# motorcontroller_10_01_2017.net
KiCad netlist of a schematic drawn in EAGLE
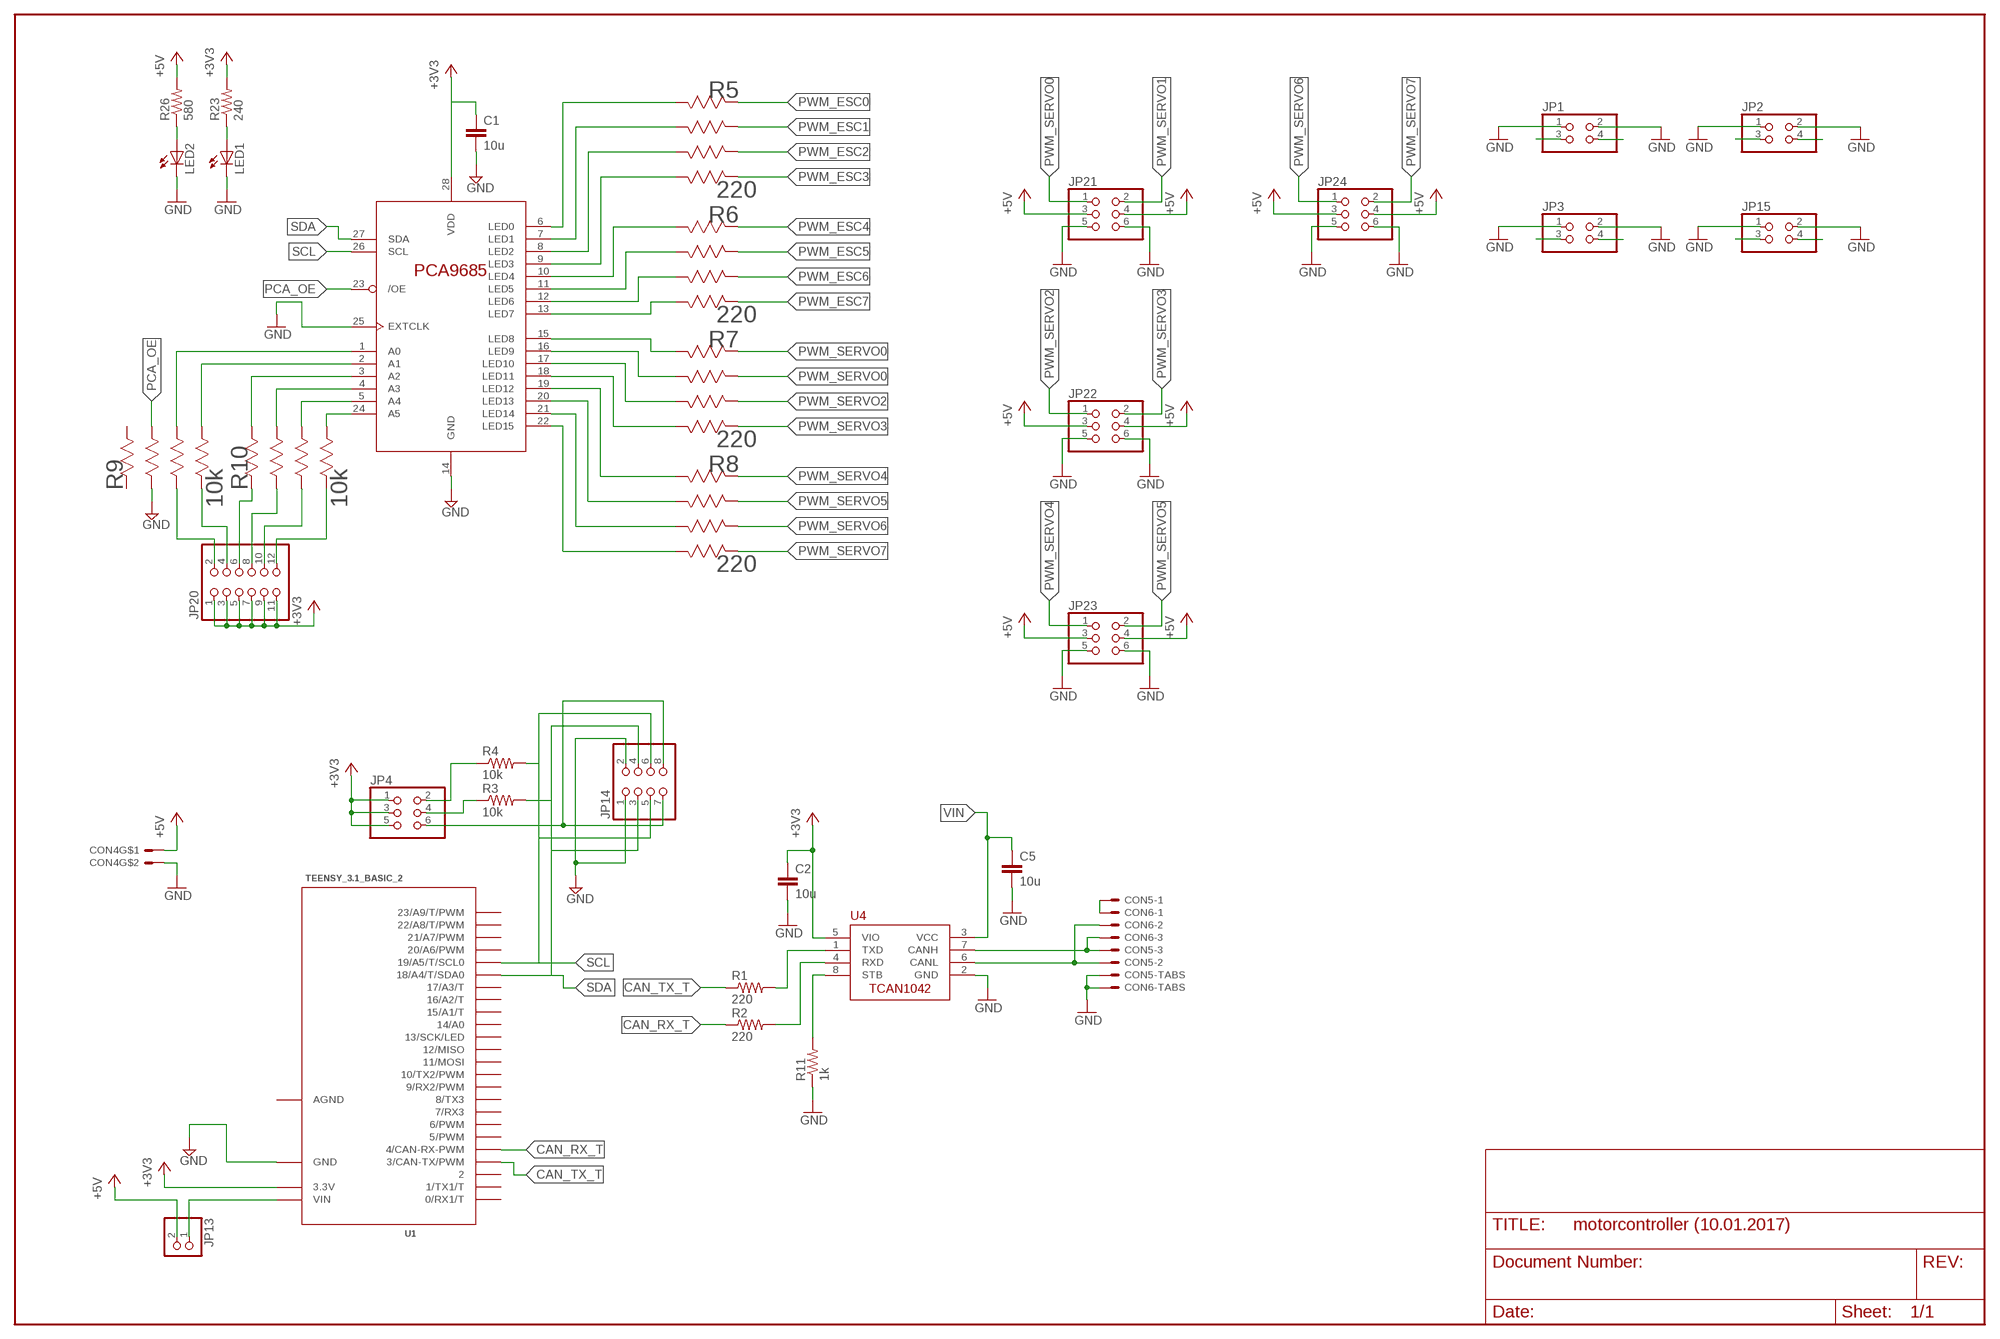
[diagram p0: schematic, sheet 1]

(export (version "E")
  (design (tool "Eeschema 10.0.6"))
  (components
    (comp (ref "C1")
      (value "10u")
      (footprint "eagle-import:C0805")
      (libsource (lib "eagle-import") (part "C-EUC0805"))
    )
    (comp (ref "C2")
      (value "10u")
      (footprint "eagle-import:C0805")
      (libsource (lib "eagle-import") (part "C-EUC0805"))
    )
    (comp (ref "C5")
      (value "10u")
      (footprint "eagle-import:C0805")
      (libsource (lib "eagle-import") (part "C-EUC0805"))
    )
    (comp (ref "CON4")
      (value "MOLEX_5566-2")
      (footprint "eagle-import:5566-2")
      (libsource (lib "eagle-import") (part "MOLEX_5566-2"))
    )
    (comp (ref "CON5")
      (value "S3B-PH-SM4-TB")
      (footprint "eagle-import:S3B-PH-SM4-TB")
      (libsource (lib "eagle-import") (part "S3B-PH-SM4-TB"))
    )
    (comp (ref "CON6")
      (value "S3B-PH-SM4-TB")
      (footprint "eagle-import:S3B-PH-SM4-TB")
      (libsource (lib "eagle-import") (part "S3B-PH-SM4-TB"))
    )
    (comp (ref "JP1")
      (value "PINHD-2X2")
      (footprint "eagle-import:2X02")
      (libsource (lib "eagle-import") (part "PINHD-2X2"))
    )
    (comp (ref "JP2")
      (value "PINHD-2X2")
      (footprint "eagle-import:2X02")
      (libsource (lib "eagle-import") (part "PINHD-2X2"))
    )
    (comp (ref "JP3")
      (value "PINHD-2X2")
      (footprint "eagle-import:2X02")
      (libsource (lib "eagle-import") (part "PINHD-2X2"))
    )
    (comp (ref "JP4")
      (value "PINHD-2X3")
      (footprint "eagle-import:2X03")
      (libsource (lib "eagle-import") (part "PINHD-2X3"))
    )
    (comp (ref "JP13")
      (value "PINHD-1X2")
      (footprint "eagle-import:1X02")
      (libsource (lib "eagle-import") (part "PINHD-1X2"))
    )
    (comp (ref "JP14")
      (value "PINHD-2X4")
      (footprint "eagle-import:2X04")
      (libsource (lib "eagle-import") (part "PINHD-2X4"))
    )
    (comp (ref "JP15")
      (value "PINHD-2X2")
      (footprint "eagle-import:2X02")
      (libsource (lib "eagle-import") (part "PINHD-2X2"))
    )
    (comp (ref "JP20")
      (value "PINHD-2X6")
      (footprint "eagle-import:2X06")
      (libsource (lib "eagle-import") (part "PINHD-2X6"))
    )
    (comp (ref "JP21")
      (value "PINHD-2X3")
      (footprint "eagle-import:2X03")
      (libsource (lib "eagle-import") (part "PINHD-2X3"))
    )
    (comp (ref "JP22")
      (value "PINHD-2X3")
      (footprint "eagle-import:2X03")
      (libsource (lib "eagle-import") (part "PINHD-2X3"))
    )
    (comp (ref "JP23")
      (value "PINHD-2X3")
      (footprint "eagle-import:2X03")
      (libsource (lib "eagle-import") (part "PINHD-2X3"))
    )
    (comp (ref "JP24")
      (value "PINHD-2X3")
      (footprint "eagle-import:2X03")
      (libsource (lib "eagle-import") (part "PINHD-2X3"))
    )
    (comp (ref "LED1")
      (value "LEDCHIPLED_1206")
      (footprint "eagle-import:CHIPLED_1206")
      (libsource (lib "eagle-import") (part "LEDCHIPLED_1206"))
    )
    (comp (ref "LED2")
      (value "LEDCHIPLED_1206")
      (footprint "eagle-import:CHIPLED_1206")
      (libsource (lib "eagle-import") (part "LEDCHIPLED_1206"))
    )
    (comp (ref "R1")
      (value "220")
      (footprint "eagle-import:R0805")
      (libsource (lib "eagle-import") (part "R-US_R0805"))
    )
    (comp (ref "R2")
      (value "220")
      (footprint "eagle-import:R0805")
      (libsource (lib "eagle-import") (part "R-US_R0805"))
    )
    (comp (ref "R3")
      (value "10k")
      (footprint "eagle-import:R1206")
      (libsource (lib "eagle-import") (part "R-US_R1206"))
    )
    (comp (ref "R4")
      (value "10k")
      (footprint "eagle-import:R1206")
      (libsource (lib "eagle-import") (part "R-US_R1206"))
    )
    (comp (ref "R5")
      (value "220")
      (footprint "eagle-import:EXBV8V-M")
      (fields (field (name "MANUFACTURER_PART_NUMBER") "EXBV8V221JV"))
      (libsource (lib "eagle-import") (part "EXB-V8V221JVEXBV8V-M"))
    )
    (comp (ref "R6")
      (value "220")
      (footprint "eagle-import:EXBV8V-M")
      (fields (field (name "MANUFACTURER_PART_NUMBER") "EXBV8V221JV"))
      (libsource (lib "eagle-import") (part "EXB-V8V221JVEXBV8V-M"))
    )
    (comp (ref "R7")
      (value "220")
      (footprint "eagle-import:EXBV8V-M")
      (fields (field (name "MANUFACTURER_PART_NUMBER") "EXBV8V221JV"))
      (libsource (lib "eagle-import") (part "EXB-V8V221JVEXBV8V-M"))
    )
    (comp (ref "R8")
      (value "220")
      (footprint "eagle-import:EXBV8V-M")
      (fields (field (name "MANUFACTURER_PART_NUMBER") "EXBV8V221JV"))
      (libsource (lib "eagle-import") (part "EXB-V8V221JVEXBV8V-M"))
    )
    (comp (ref "R9")
      (value "10k")
      (footprint "eagle-import:EXBV8V-M")
      (fields (field (name "MANUFACTURER_PART_NUMBER") "EXBV8V221JV"))
      (libsource (lib "eagle-import") (part "EXB-V8V221JVEXBV8V-M"))
    )
    (comp (ref "R10")
      (value "10k")
      (footprint "eagle-import:EXBV8V-M")
      (fields (field (name "MANUFACTURER_PART_NUMBER") "EXBV8V221JV"))
      (libsource (lib "eagle-import") (part "EXB-V8V221JVEXBV8V-M"))
    )
    (comp (ref "R11")
      (value "1k")
      (footprint "eagle-import:R0805")
      (libsource (lib "eagle-import") (part "R-US_R0805"))
    )
    (comp (ref "R23")
      (value "240")
      (footprint "eagle-import:R1206")
      (libsource (lib "eagle-import") (part "R-US_R1206"))
    )
    (comp (ref "R26")
      (value "580")
      (footprint "eagle-import:R1206")
      (libsource (lib "eagle-import") (part "R-US_R1206"))
    )
    (comp (ref "U1")
      (value "TEENSY_3.1_BASIC_2")
      (footprint "eagle-import:TEENSY_3.1_BASIC_2")
      (libsource (lib "eagle-import") (part "TEENSY_3.1_BASIC_2"))
    )
    (comp (ref "U2")
      (value "PCA9685PW")
      (footprint "eagle-import:TSSOP28")
      (libsource (lib "eagle-import") (part "PCA9685PW"))
    )
    (comp (ref "U4")
      (value "TCAN1042HVDR")
      (footprint "eagle-import:SO-8")
      (libsource (lib "eagle-import") (part "TCAN1042HVDR"))
    )
  )
  (nets
    (net (code "1") (name "+3V3") (class "Default")
      (node (ref "C1") (pin "1") (pinfunction "1_1") (pintype "passive"))
      (node (ref "C2") (pin "1") (pinfunction "1_1") (pintype "passive"))
      (node (ref "JP20") (pin "1") (pinfunction "1_1") (pintype "passive"))
      (node (ref "JP20") (pin "11") (pinfunction "11_11") (pintype "passive"))
      (node (ref "JP20") (pin "3") (pinfunction "3_3") (pintype "passive"))
      (node (ref "JP20") (pin "5") (pinfunction "5_5") (pintype "passive"))
      (node (ref "JP20") (pin "7") (pinfunction "7_7") (pintype "passive"))
      (node (ref "JP20") (pin "9") (pinfunction "9_9") (pintype "passive"))
      (node (ref "JP4") (pin "1") (pinfunction "1_1") (pintype "passive"))
      (node (ref "JP4") (pin "3") (pinfunction "3_3") (pintype "passive"))
      (node (ref "JP4") (pin "5") (pinfunction "5_5") (pintype "passive"))
      (node (ref "R23") (pin "2") (pinfunction "2_2") (pintype "passive"))
      (node (ref "U1") (pin "3.3V") (pinfunction "3.3V_3.3V") (pintype "power_in"))
      (node (ref "U2") (pin "28") (pinfunction "VDD_28") (pintype "power_in"))
      (node (ref "U4") (pin "5") (pinfunction "VIO_5") (pintype "bidirectional"))
    )
    (net (code "2") (name "+5V") (class "Default")
      (node (ref "CON4") (pin "1") (pinfunction "S_1") (pintype "passive"))
      (node (ref "JP13") (pin "2") (pinfunction "2_2") (pintype "passive"))
      (node (ref "JP21") (pin "3") (pinfunction "3_3") (pintype "passive"))
      (node (ref "JP21") (pin "4") (pinfunction "4_4") (pintype "passive"))
      (node (ref "JP22") (pin "3") (pinfunction "3_3") (pintype "passive"))
      (node (ref "JP22") (pin "4") (pinfunction "4_4") (pintype "passive"))
      (node (ref "JP23") (pin "3") (pinfunction "3_3") (pintype "passive"))
      (node (ref "JP23") (pin "4") (pinfunction "4_4") (pintype "passive"))
      (node (ref "JP24") (pin "3") (pinfunction "3_3") (pintype "passive"))
      (node (ref "JP24") (pin "4") (pinfunction "4_4") (pintype "passive"))
      (node (ref "R26") (pin "2") (pinfunction "2_2") (pintype "passive"))
    )
    (net (code "3") (name "/AGND") (class "Default")
      (node (ref "U1") (pin "AGND") (pinfunction "AGND_AGND") (pintype "power_in"))
    )
    (net (code "4") (name "CAN_RX_T") (class "Default")
      (node (ref "R2") (pin "1") (pinfunction "1_1") (pintype "passive"))
      (node (ref "U1") (pin "4") (pinfunction "4/CAN-RX-PWM_4") (pintype "bidirectional"))
    )
    (net (code "5") (name "CAN_TX_T") (class "Default")
      (node (ref "R1") (pin "1") (pinfunction "1_1") (pintype "passive"))
      (node (ref "U1") (pin "3") (pinfunction "3/CAN-TX/PWM_3") (pintype "bidirectional"))
    )
    (net (code "6") (name "GND") (class "Default")
      (node (ref "C1") (pin "2") (pinfunction "2_2") (pintype "passive"))
      (node (ref "C2") (pin "2") (pinfunction "2_2") (pintype "passive"))
      (node (ref "C5") (pin "2") (pinfunction "2_2") (pintype "passive"))
      (node (ref "CON4") (pin "2") (pinfunction "S_2") (pintype "passive"))
      (node (ref "CON5") (pin "P$4") (pinfunction "S_P$4") (pintype "passive"))
      (node (ref "CON5") (pin "P$5") (pinfunction "S_P$5") (pintype "passive"))
      (node (ref "CON6") (pin "P$4") (pinfunction "S_P$4") (pintype "passive"))
      (node (ref "CON6") (pin "P$5") (pinfunction "S_P$5") (pintype "passive"))
      (node (ref "JP1") (pin "1") (pinfunction "1_1") (pintype "passive"))
      (node (ref "JP1") (pin "2") (pinfunction "2_2") (pintype "passive"))
      (node (ref "JP14") (pin "1") (pinfunction "1_1") (pintype "passive"))
      (node (ref "JP14") (pin "2") (pinfunction "2_2") (pintype "passive"))
      (node (ref "JP15") (pin "1") (pinfunction "1_1") (pintype "passive"))
      (node (ref "JP15") (pin "2") (pinfunction "2_2") (pintype "passive"))
      (node (ref "JP2") (pin "1") (pinfunction "1_1") (pintype "passive"))
      (node (ref "JP2") (pin "2") (pinfunction "2_2") (pintype "passive"))
      (node (ref "JP21") (pin "5") (pinfunction "5_5") (pintype "passive"))
      (node (ref "JP21") (pin "6") (pinfunction "6_6") (pintype "passive"))
      (node (ref "JP22") (pin "5") (pinfunction "5_5") (pintype "passive"))
      (node (ref "JP22") (pin "6") (pinfunction "6_6") (pintype "passive"))
      (node (ref "JP23") (pin "5") (pinfunction "5_5") (pintype "passive"))
      (node (ref "JP23") (pin "6") (pinfunction "6_6") (pintype "passive"))
      (node (ref "JP24") (pin "5") (pinfunction "5_5") (pintype "passive"))
      (node (ref "JP24") (pin "6") (pinfunction "6_6") (pintype "passive"))
      (node (ref "JP3") (pin "1") (pinfunction "1_1") (pintype "passive"))
      (node (ref "JP3") (pin "2") (pinfunction "2_2") (pintype "passive"))
      (node (ref "LED1") (pin "C") (pinfunction "C_C") (pintype "passive"))
      (node (ref "LED2") (pin "C") (pinfunction "C_C") (pintype "passive"))
      (node (ref "R11") (pin "1") (pinfunction "1_1") (pintype "passive"))
      (node (ref "R9") (pin "2") (pinfunction "23_2") (pintype "passive"))
      (node (ref "U1") (pin "GND") (pinfunction "GND_GND") (pintype "power_in"))
      (node (ref "U2") (pin "14") (pinfunction "GND_14") (pintype "power_in"))
      (node (ref "U2") (pin "25") (pinfunction "EXTCLK_25") (pintype "input"))
      (node (ref "U4") (pin "2") (pinfunction "GND_2") (pintype "bidirectional"))
    )
    (net (code "7") (name "Net-(CON5A-S)") (class "Default")
      (node (ref "CON5") (pin "P$1") (pinfunction "S_P$1") (pintype "passive"))
      (node (ref "CON6") (pin "P$1") (pinfunction "S_P$1") (pintype "passive"))
    )
    (net (code "8") (name "Net-(CON5B-S)") (class "Default")
      (node (ref "CON5") (pin "P$2") (pinfunction "S_P$2") (pintype "passive"))
      (node (ref "CON6") (pin "P$2") (pinfunction "S_P$2") (pintype "passive"))
      (node (ref "U4") (pin "6") (pinfunction "CANL_6") (pintype "bidirectional"))
    )
    (net (code "9") (name "Net-(CON5C-S)") (class "Default")
      (node (ref "CON5") (pin "P$3") (pinfunction "S_P$3") (pintype "passive"))
      (node (ref "CON6") (pin "P$3") (pinfunction "S_P$3") (pintype "passive"))
      (node (ref "U4") (pin "7") (pinfunction "CANH_7") (pintype "bidirectional"))
    )
    (net (code "10") (name "Net-(JP4-Pad2)") (class "Default")
      (node (ref "JP4") (pin "2") (pinfunction "2_2") (pintype "passive"))
      (node (ref "R4") (pin "1") (pinfunction "1_1") (pintype "passive"))
    )
    (net (code "11") (name "Net-(JP4-Pad4)") (class "Default")
      (node (ref "JP4") (pin "4") (pinfunction "4_4") (pintype "passive"))
      (node (ref "R3") (pin "1") (pinfunction "1_1") (pintype "passive"))
    )
    (net (code "12") (name "Net-(JP14-Pad7)") (class "Default")
      (node (ref "JP14") (pin "7") (pinfunction "7_7") (pintype "passive"))
      (node (ref "JP14") (pin "8") (pinfunction "8_8") (pintype "passive"))
      (node (ref "JP4") (pin "6") (pinfunction "6_6") (pintype "passive"))
    )
    (net (code "13") (name "Net-(LED1-PadA)") (class "Default")
      (node (ref "LED1") (pin "A") (pinfunction "A_A") (pintype "passive"))
      (node (ref "R23") (pin "1") (pinfunction "1_1") (pintype "passive"))
    )
    (net (code "14") (name "Net-(LED2-PadA)") (class "Default")
      (node (ref "LED2") (pin "A") (pinfunction "A_A") (pintype "passive"))
      (node (ref "R26") (pin "1") (pinfunction "1_1") (pintype "passive"))
    )
    (net (code "15") (name "Net-(R5-58)") (class "Default")
      (node (ref "R5") (pin "5") (pinfunction "58_5") (pintype "passive"))
      (node (ref "U2") (pin "9") (pinfunction "LED3_9") (pintype "bidirectional"))
    )
    (net (code "16") (name "Net-(R5-66)") (class "Default")
      (node (ref "R5") (pin "6") (pinfunction "66_6") (pintype "passive"))
      (node (ref "U2") (pin "8") (pinfunction "LED2_8") (pintype "bidirectional"))
    )
    (net (code "17") (name "Net-(R5-74)") (class "Default")
      (node (ref "R5") (pin "7") (pinfunction "74_7") (pintype "passive"))
      (node (ref "U2") (pin "7") (pinfunction "LED1_7") (pintype "bidirectional"))
    )
    (net (code "18") (name "Net-(R5-82)") (class "Default")
      (node (ref "R5") (pin "8") (pinfunction "82_8") (pintype "passive"))
      (node (ref "U2") (pin "6") (pinfunction "LED0_6") (pintype "bidirectional"))
    )
    (net (code "19") (name "Net-(R6-58)") (class "Default")
      (node (ref "R6") (pin "5") (pinfunction "58_5") (pintype "passive"))
      (node (ref "U2") (pin "13") (pinfunction "LED7_13") (pintype "bidirectional"))
    )
    (net (code "20") (name "Net-(R6-66)") (class "Default")
      (node (ref "R6") (pin "6") (pinfunction "66_6") (pintype "passive"))
      (node (ref "U2") (pin "12") (pinfunction "LED6_12") (pintype "bidirectional"))
    )
    (net (code "21") (name "Net-(R6-74)") (class "Default")
      (node (ref "R6") (pin "7") (pinfunction "74_7") (pintype "passive"))
      (node (ref "U2") (pin "11") (pinfunction "LED5_11") (pintype "bidirectional"))
    )
    (net (code "22") (name "Net-(R6-82)") (class "Default")
      (node (ref "R6") (pin "8") (pinfunction "82_8") (pintype "passive"))
      (node (ref "U2") (pin "10") (pinfunction "LED4_10") (pintype "bidirectional"))
    )
    (net (code "23") (name "Net-(R7-58)") (class "Default")
      (node (ref "R7") (pin "5") (pinfunction "58_5") (pintype "passive"))
      (node (ref "U2") (pin "18") (pinfunction "LED11_18") (pintype "bidirectional"))
    )
    (net (code "24") (name "Net-(R7-66)") (class "Default")
      (node (ref "R7") (pin "6") (pinfunction "66_6") (pintype "passive"))
      (node (ref "U2") (pin "17") (pinfunction "LED10_17") (pintype "bidirectional"))
    )
    (net (code "25") (name "Net-(R7-74)") (class "Default")
      (node (ref "R7") (pin "7") (pinfunction "74_7") (pintype "passive"))
      (node (ref "U2") (pin "16") (pinfunction "LED9_16") (pintype "bidirectional"))
    )
    (net (code "26") (name "Net-(R7-82)") (class "Default")
      (node (ref "R7") (pin "8") (pinfunction "82_8") (pintype "passive"))
      (node (ref "U2") (pin "15") (pinfunction "LED8_15") (pintype "bidirectional"))
    )
    (net (code "27") (name "Net-(R8-58)") (class "Default")
      (node (ref "R8") (pin "5") (pinfunction "58_5") (pintype "passive"))
      (node (ref "U2") (pin "22") (pinfunction "LED15_22") (pintype "bidirectional"))
    )
    (net (code "28") (name "Net-(R8-66)") (class "Default")
      (node (ref "R8") (pin "6") (pinfunction "66_6") (pintype "passive"))
      (node (ref "U2") (pin "21") (pinfunction "LED14_21") (pintype "bidirectional"))
    )
    (net (code "29") (name "Net-(R8-74)") (class "Default")
      (node (ref "R8") (pin "7") (pinfunction "74_7") (pintype "passive"))
      (node (ref "U2") (pin "20") (pinfunction "LED13_20") (pintype "bidirectional"))
    )
    (net (code "30") (name "Net-(R8-82)") (class "Default")
      (node (ref "R8") (pin "8") (pinfunction "82_8") (pintype "passive"))
      (node (ref "U2") (pin "19") (pinfunction "LED12_19") (pintype "bidirectional"))
    )
    (net (code "31") (name "Net-(R9-35)") (class "Default")
      (node (ref "JP20") (pin "2") (pinfunction "2_2") (pintype "passive"))
      (node (ref "R9") (pin "3") (pinfunction "35_3") (pintype "passive"))
    )
    (net (code "32") (name "Net-(R9-47)") (class "Default")
      (node (ref "JP20") (pin "4") (pinfunction "4_4") (pintype "passive"))
      (node (ref "R9") (pin "4") (pinfunction "47_4") (pintype "passive"))
    )
    (net (code "33") (name "Net-(R9-58)") (class "Default")
      (node (ref "R9") (pin "5") (pinfunction "58_5") (pintype "passive"))
      (node (ref "U2") (pin "2") (pinfunction "A1_2") (pintype "bidirectional"))
    )
    (net (code "34") (name "Net-(R9-66)") (class "Default")
      (node (ref "R9") (pin "6") (pinfunction "66_6") (pintype "passive"))
      (node (ref "U2") (pin "1") (pinfunction "A0_1") (pintype "bidirectional"))
    )
    (net (code "35") (name "Net-(R10-11)") (class "Default")
      (node (ref "JP20") (pin "6") (pinfunction "6_6") (pintype "passive"))
      (node (ref "R10") (pin "1") (pinfunction "11_1") (pintype "passive"))
    )
    (net (code "36") (name "Net-(R10-23)") (class "Default")
      (node (ref "JP20") (pin "8") (pinfunction "8_8") (pintype "passive"))
      (node (ref "R10") (pin "2") (pinfunction "23_2") (pintype "passive"))
    )
    (net (code "37") (name "Net-(R10-35)") (class "Default")
      (node (ref "JP20") (pin "10") (pinfunction "10_10") (pintype "passive"))
      (node (ref "R10") (pin "3") (pinfunction "35_3") (pintype "passive"))
    )
    (net (code "38") (name "Net-(R10-47)") (class "Default")
      (node (ref "JP20") (pin "12") (pinfunction "12_12") (pintype "passive"))
      (node (ref "R10") (pin "4") (pinfunction "47_4") (pintype "passive"))
    )
    (net (code "39") (name "Net-(R10-58)") (class "Default")
      (node (ref "R10") (pin "5") (pinfunction "58_5") (pintype "passive"))
      (node (ref "U2") (pin "24") (pinfunction "A5_24") (pintype "bidirectional"))
    )
    (net (code "40") (name "Net-(R10-66)") (class "Default")
      (node (ref "R10") (pin "6") (pinfunction "66_6") (pintype "passive"))
      (node (ref "U2") (pin "5") (pinfunction "A4_5") (pintype "bidirectional"))
    )
    (net (code "41") (name "Net-(R10-74)") (class "Default")
      (node (ref "R10") (pin "7") (pinfunction "74_7") (pintype "passive"))
      (node (ref "U2") (pin "4") (pinfunction "A3_4") (pintype "bidirectional"))
    )
    (net (code "42") (name "Net-(R10-82)") (class "Default")
      (node (ref "R10") (pin "8") (pinfunction "82_8") (pintype "passive"))
      (node (ref "U2") (pin "3") (pinfunction "A2_3") (pintype "bidirectional"))
    )
    (net (code "43") (name "Net-(U4-RXD)") (class "Default")
      (node (ref "R2") (pin "2") (pinfunction "2_2") (pintype "passive"))
      (node (ref "U4") (pin "4") (pinfunction "RXD_4") (pintype "bidirectional"))
    )
    (net (code "44") (name "Net-(U4-STB)") (class "Default")
      (node (ref "R11") (pin "2") (pinfunction "2_2") (pintype "passive"))
      (node (ref "U4") (pin "8") (pinfunction "STB_8") (pintype "bidirectional"))
    )
    (net (code "45") (name "Net-(U4-TXD)") (class "Default")
      (node (ref "R1") (pin "2") (pinfunction "2_2") (pintype "passive"))
      (node (ref "U4") (pin "1") (pinfunction "TXD_1") (pintype "bidirectional"))
    )
    (net (code "46") (name "PCA_OE") (class "Default")
      (node (ref "R9") (pin "7") (pinfunction "74_7") (pintype "passive"))
      (node (ref "U2") (pin "23") (pinfunction "/OE_23") (pintype "bidirectional"))
    )
    (net (code "47") (name "PWM_ESC0") (class "Default")
      (node (ref "JP15") (pin "4") (pinfunction "4_4") (pintype "passive"))
      (node (ref "R5") (pin "1") (pinfunction "11_1") (pintype "passive"))
    )
    (net (code "48") (name "PWM_ESC1") (class "Default")
      (node (ref "JP15") (pin "3") (pinfunction "3_3") (pintype "passive"))
      (node (ref "R5") (pin "2") (pinfunction "23_2") (pintype "passive"))
    )
    (net (code "49") (name "PWM_ESC2") (class "Default")
      (node (ref "JP1") (pin "4") (pinfunction "4_4") (pintype "passive"))
      (node (ref "R5") (pin "3") (pinfunction "35_3") (pintype "passive"))
    )
    (net (code "50") (name "PWM_ESC3") (class "Default")
      (node (ref "JP1") (pin "3") (pinfunction "3_3") (pintype "passive"))
      (node (ref "R5") (pin "4") (pinfunction "47_4") (pintype "passive"))
    )
    (net (code "51") (name "PWM_ESC4") (class "Default")
      (node (ref "JP2") (pin "4") (pinfunction "4_4") (pintype "passive"))
      (node (ref "R6") (pin "1") (pinfunction "11_1") (pintype "passive"))
    )
    (net (code "52") (name "PWM_ESC5") (class "Default")
      (node (ref "JP2") (pin "3") (pinfunction "3_3") (pintype "passive"))
      (node (ref "R6") (pin "2") (pinfunction "23_2") (pintype "passive"))
    )
    (net (code "53") (name "PWM_ESC6") (class "Default")
      (node (ref "JP3") (pin "4") (pinfunction "4_4") (pintype "passive"))
      (node (ref "R6") (pin "3") (pinfunction "35_3") (pintype "passive"))
    )
    (net (code "54") (name "PWM_ESC7") (class "Default")
      (node (ref "JP3") (pin "3") (pinfunction "3_3") (pintype "passive"))
      (node (ref "R6") (pin "4") (pinfunction "47_4") (pintype "passive"))
    )
    (net (code "55") (name "PWM_SERVO0") (class "Default")
      (node (ref "JP21") (pin "1") (pinfunction "1_1") (pintype "passive"))
      (node (ref "R7") (pin "1") (pinfunction "11_1") (pintype "passive"))
    )
    (net (code "56") (name "PWM_SERVO1") (class "Default")
      (node (ref "JP21") (pin "2") (pinfunction "2_2") (pintype "passive"))
      (node (ref "R7") (pin "2") (pinfunction "23_2") (pintype "passive"))
    )
    (net (code "57") (name "PWM_SERVO2") (class "Default")
      (node (ref "JP22") (pin "1") (pinfunction "1_1") (pintype "passive"))
      (node (ref "R7") (pin "3") (pinfunction "35_3") (pintype "passive"))
    )
    (net (code "58") (name "PWM_SERVO3") (class "Default")
      (node (ref "JP22") (pin "2") (pinfunction "2_2") (pintype "passive"))
      (node (ref "R7") (pin "4") (pinfunction "47_4") (pintype "passive"))
    )
    (net (code "59") (name "PWM_SERVO4") (class "Default")
      (node (ref "JP23") (pin "1") (pinfunction "1_1") (pintype "passive"))
      (node (ref "R8") (pin "1") (pinfunction "11_1") (pintype "passive"))
    )
    (net (code "60") (name "PWM_SERVO5") (class "Default")
      (node (ref "JP23") (pin "2") (pinfunction "2_2") (pintype "passive"))
      (node (ref "R8") (pin "2") (pinfunction "23_2") (pintype "passive"))
    )
    (net (code "61") (name "PWM_SERVO6") (class "Default")
      (node (ref "JP24") (pin "1") (pinfunction "1_1") (pintype "passive"))
      (node (ref "R8") (pin "3") (pinfunction "35_3") (pintype "passive"))
    )
    (net (code "62") (name "PWM_SERVO7") (class "Default")
      (node (ref "JP24") (pin "2") (pinfunction "2_2") (pintype "passive"))
      (node (ref "R8") (pin "4") (pinfunction "47_4") (pintype "passive"))
    )
    (net (code "63") (name "SCL") (class "Default")
      (node (ref "JP14") (pin "5") (pinfunction "5_5") (pintype "passive"))
      (node (ref "JP14") (pin "6") (pinfunction "6_6") (pintype "passive"))
      (node (ref "R4") (pin "2") (pinfunction "2_2") (pintype "passive"))
      (node (ref "U1") (pin "19/A5") (pinfunction "19/A5/T/SCL0_19/A5") (pintype "bidirectional"))
      (node (ref "U2") (pin "26") (pinfunction "SCL_26") (pintype "bidirectional"))
    )
    (net (code "64") (name "SDA") (class "Default")
      (node (ref "JP14") (pin "3") (pinfunction "3_3") (pintype "passive"))
      (node (ref "JP14") (pin "4") (pinfunction "4_4") (pintype "passive"))
      (node (ref "R3") (pin "2") (pinfunction "2_2") (pintype "passive"))
      (node (ref "U1") (pin "18/A4") (pinfunction "18/A4/T/SDA0_18/A4") (pintype "bidirectional"))
      (node (ref "U2") (pin "27") (pinfunction "SDA_27") (pintype "bidirectional"))
    )
    (net (code "65") (name "VIN") (class "Default")
      (node (ref "C5") (pin "1") (pinfunction "1_1") (pintype "passive"))
      (node (ref "JP13") (pin "1") (pinfunction "1_1") (pintype "passive"))
      (node (ref "U1") (pin "VIN") (pinfunction "VIN_VIN") (pintype "power_in"))
      (node (ref "U4") (pin "3") (pinfunction "VCC_3") (pintype "bidirectional"))
    )
    (net (code "66") (name "unconnected-(R9-11-Pad1)") (class "Default")
      (node (ref "R9") (pin "1") (pinfunction "11_1") (pintype "passive"))
    )
    (net (code "67") (name "unconnected-(R9-82-Pad8)") (class "Default")
      (node (ref "R9") (pin "8") (pinfunction "82_8") (pintype "passive"))
    )
    (net (code "68") (name "unconnected-(U1-0{slash}RX1{slash}T-Pad0)") (class "Default")
      (node (ref "U1") (pin "0") (pinfunction "0/RX1/T_0") (pintype "bidirectional"))
    )
    (net (code "69") (name "unconnected-(U1-1{slash}TX1{slash}T-Pad1)") (class "Default")
      (node (ref "U1") (pin "1") (pinfunction "1/TX1/T_1") (pintype "bidirectional"))
    )
    (net (code "70") (name "unconnected-(U1-5{slash}PWM-Pad5)") (class "Default")
      (node (ref "U1") (pin "5") (pinfunction "5/PWM_5") (pintype "bidirectional"))
    )
    (net (code "71") (name "unconnected-(U1-6{slash}PWM-Pad6)") (class "Default")
      (node (ref "U1") (pin "6") (pinfunction "6/PWM_6") (pintype "bidirectional"))
    )
    (net (code "72") (name "unconnected-(U1-7{slash}RX3-Pad7)") (class "Default")
      (node (ref "U1") (pin "7") (pinfunction "7/RX3_7") (pintype "bidirectional"))
    )
    (net (code "73") (name "unconnected-(U1-8{slash}TX3-Pad8)") (class "Default")
      (node (ref "U1") (pin "8") (pinfunction "8/TX3_8") (pintype "bidirectional"))
    )
    (net (code "74") (name "unconnected-(U1-9{slash}RX2{slash}PWM-Pad9)") (class "Default")
      (node (ref "U1") (pin "9") (pinfunction "9/RX2/PWM_9") (pintype "bidirectional"))
    )
    (net (code "75") (name "unconnected-(U1-10{slash}TX2{slash}PWM-Pad10)") (class "Default")
      (node (ref "U1") (pin "10") (pinfunction "10/TX2/PWM_10") (pintype "bidirectional"))
    )
    (net (code "76") (name "unconnected-(U1-11{slash}MOSI-Pad11)") (class "Default")
      (node (ref "U1") (pin "11") (pinfunction "11/MOSI_11") (pintype "bidirectional"))
    )
    (net (code "77") (name "unconnected-(U1-12{slash}MISO-Pad12)") (class "Default")
      (node (ref "U1") (pin "12") (pinfunction "12/MISO_12") (pintype "bidirectional"))
    )
    (net (code "78") (name "unconnected-(U1-13{slash}SCK{slash}LED-Pad13)") (class "Default")
      (node (ref "U1") (pin "13") (pinfunction "13/SCK/LED_13") (pintype "bidirectional"))
    )
    (net (code "79") (name "unconnected-(U1-15{slash}A1{slash}T-Pad15{slash}A1)") (class "Default")
      (node (ref "U1") (pin "15/A1") (pinfunction "15/A1/T_15/A1") (pintype "bidirectional"))
    )
    (net (code "80") (name "unconnected-(U1-16{slash}A2{slash}T-Pad16{slash}A2)") (class "Default")
      (node (ref "U1") (pin "16/A2") (pinfunction "16/A2/T_16/A2") (pintype "bidirectional"))
    )
    (net (code "81") (name "unconnected-(U1-17{slash}A3{slash}T-Pad17{slash}A3)") (class "Default")
      (node (ref "U1") (pin "17/A3") (pinfunction "17/A3/T_17/A3") (pintype "bidirectional"))
    )
    (net (code "82") (name "unconnected-(U1-20{slash}A6{slash}PWM-Pad20{slash}A6)") (class "Default")
      (node (ref "U1") (pin "20/A6") (pinfunction "20/A6/PWM_20/A6") (pintype "bidirectional"))
    )
    (net (code "83") (name "unconnected-(U1-21{slash}A7{slash}PWM-Pad21{slash}A7)") (class "Default")
      (node (ref "U1") (pin "21/A7") (pinfunction "21/A7/PWM_21/A7") (pintype "bidirectional"))
    )
    (net (code "84") (name "unconnected-(U1-22{slash}A8{slash}T{slash}PWM-Pad22{slash}A8)") (class "Default")
      (node (ref "U1") (pin "22/A8") (pinfunction "22/A8/T/PWM_22/A8") (pintype "bidirectional"))
    )
    (net (code "85") (name "unconnected-(U1-23{slash}A9{slash}T{slash}PWM-Pad23{slash}A9)") (class "Default")
      (node (ref "U1") (pin "23/A9") (pinfunction "23/A9/T/PWM_23/A9") (pintype "bidirectional"))
    )
    (net (code "86") (name "unconnected-(U1-Pad2)") (class "Default")
      (node (ref "U1") (pin "2") (pinfunction "2_2") (pintype "bidirectional"))
    )
    (net (code "87") (name "unconnected-(U1-Pad14{slash}A0)") (class "Default")
      (node (ref "U1") (pin "14/A0") (pinfunction "14/A0_14/A0") (pintype "bidirectional"))
    )
  )
)
